# 14_RK3568_USBPCIeSATA_PHY.net
KiCad netlist of a schematic drawn in Altium Designer
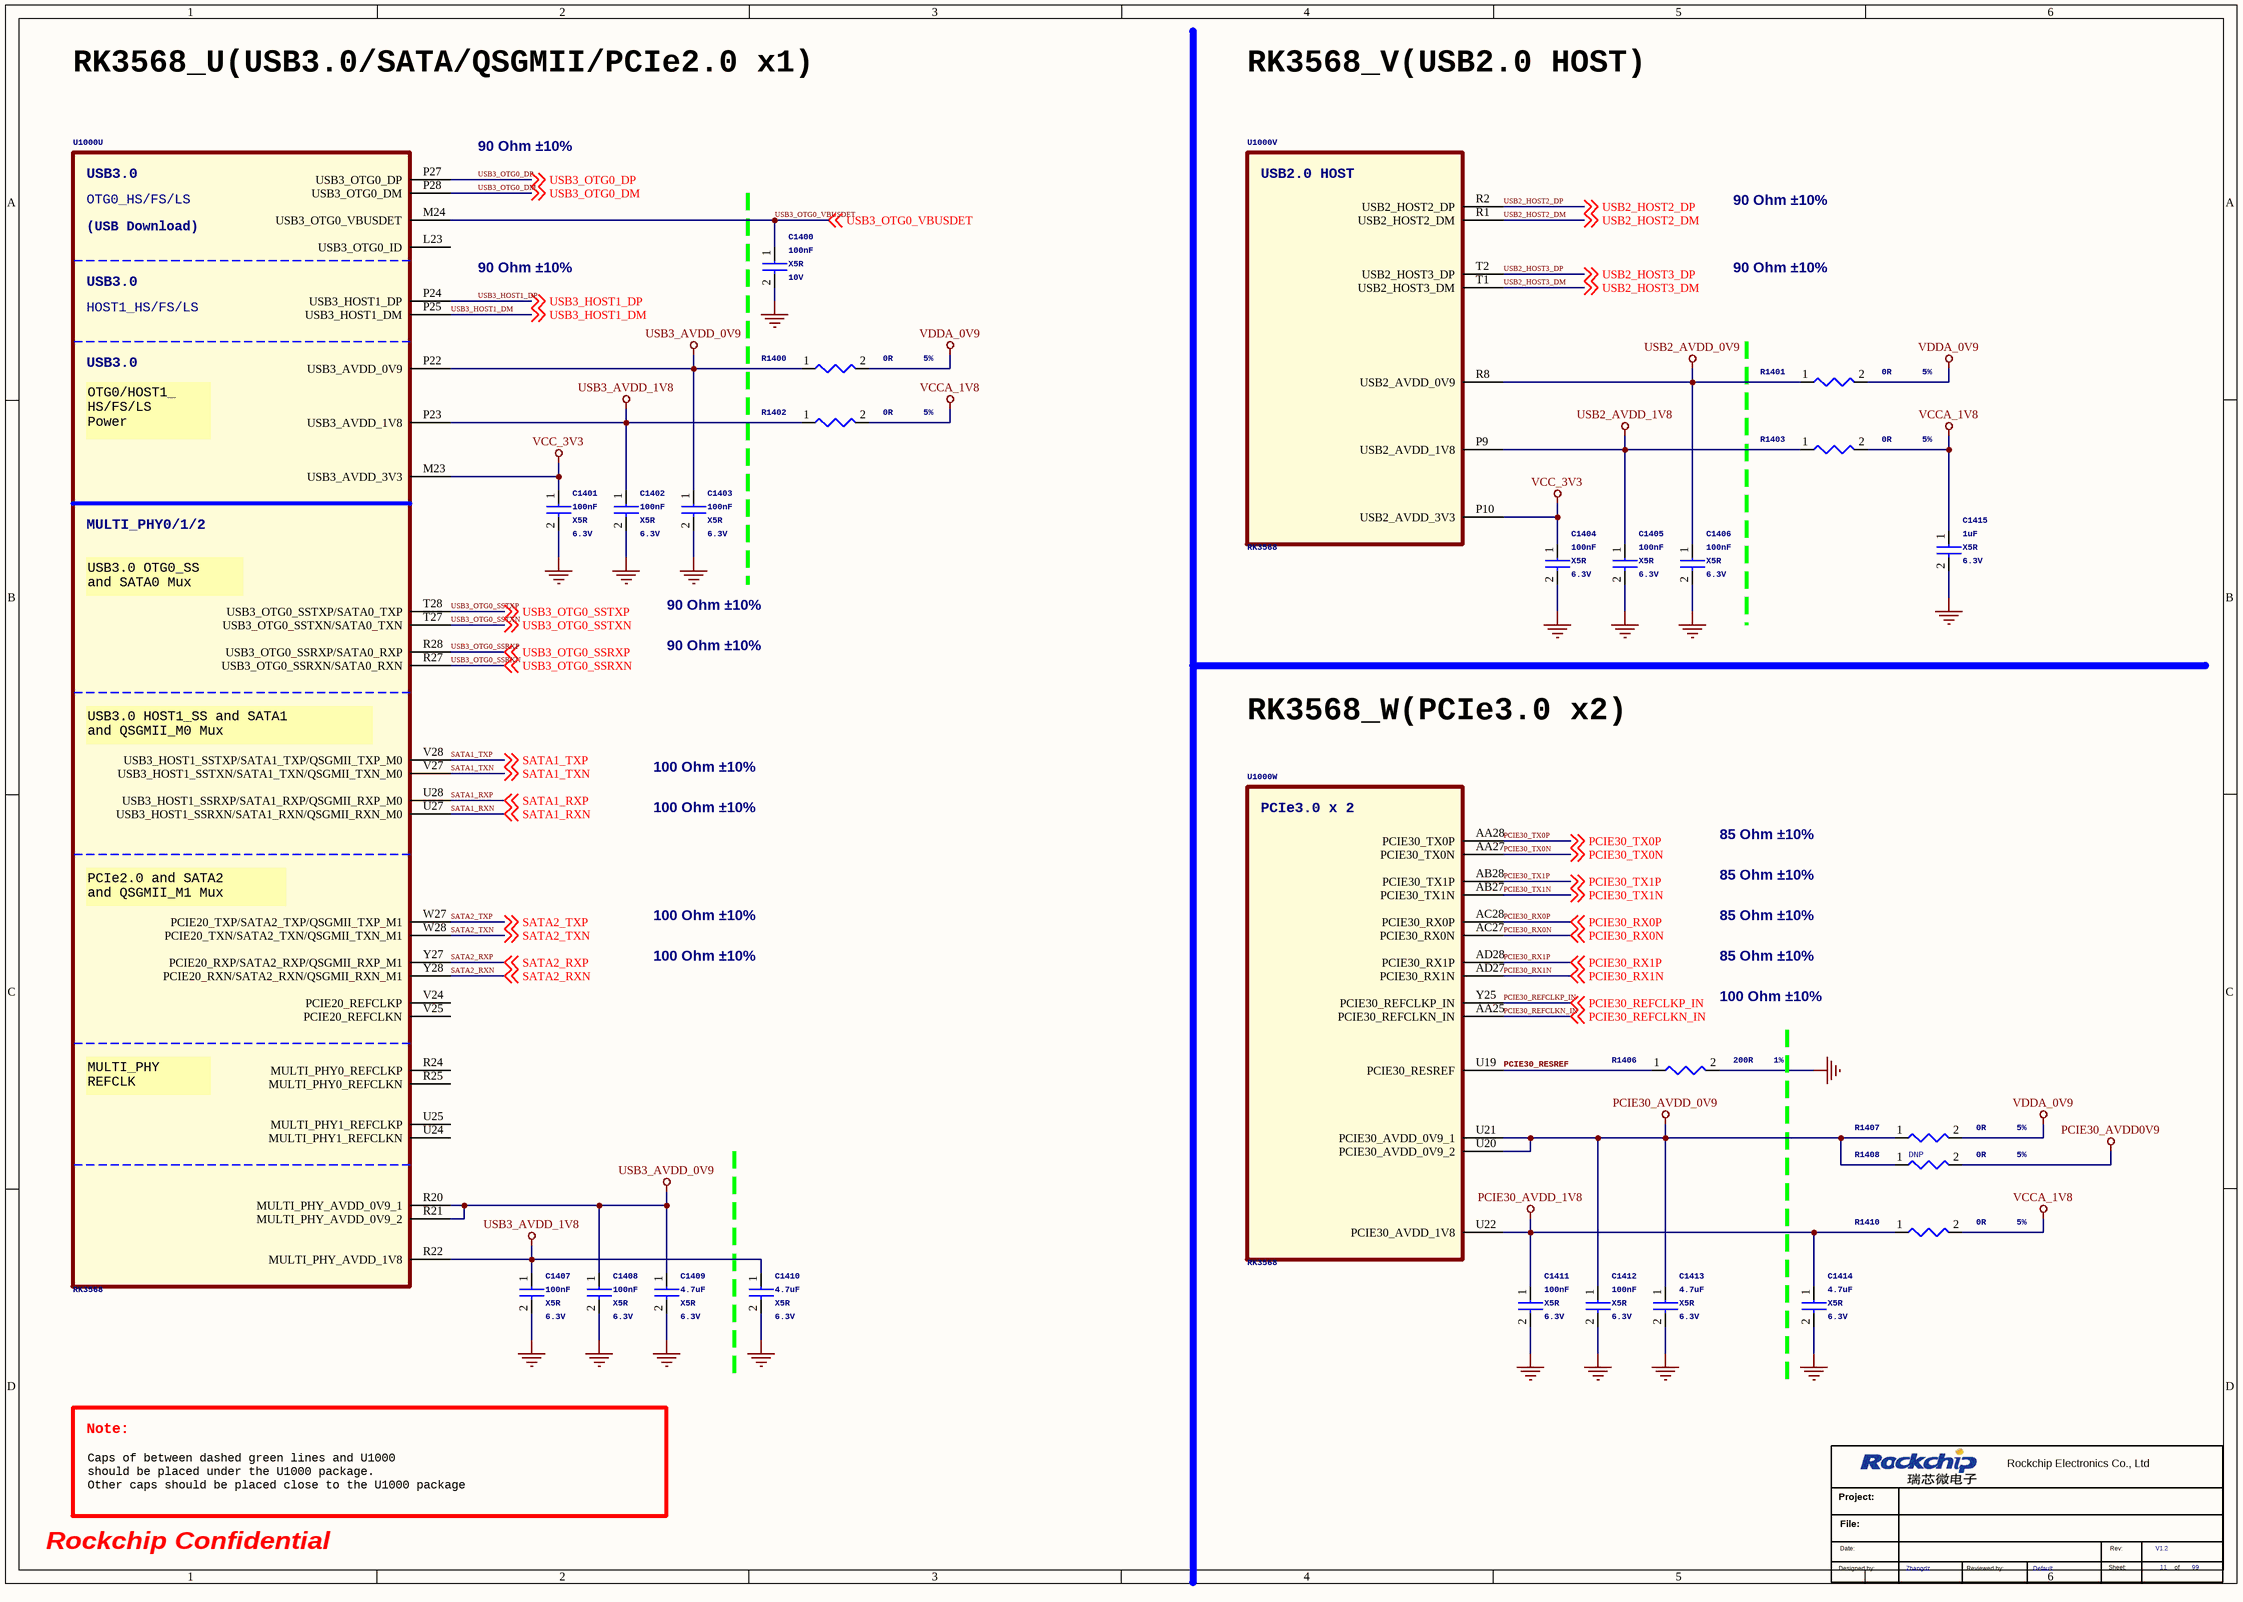
[diagram p0: 14.RK3568_USBPCIeSATA PHY.SchDoc]

(export (version "E")
  (design (tool "Eeschema 10.0.6"))
  (components
    (comp (ref "*")
      (value "Rockchip_new")
      (fields
        (field (name "SCHEMATIC PAGE COUNT") "99")
        (field (name "SCHEMATIC PAGE NUMBER") "11")
        (field (name "DESIGNER") "Zhangdz")
        (field (name "REVISION") "V1.2")
        (field (name "CHECK") "Default")
      )
      (libsource (lib "*") (part "Rockchip_new"))
    )
    (comp (ref "C1400")
      (value "100nF")
      (footprint "C0402")
      (description "cap,100.00nF,+/-10%,10V,X5R,C0402")
      (fields
        (field (name "VOLTAGE") "10V")
        (field (name "DIELECTRIC") "X5R")
        (field (name "MANUFACTURER") "TDK")
        (field (name "TOLERANCE") "10%")
        (field (name "CREATED BY") "JJJ")
      )
      (libsource (lib "*") (part "CAP NP"))
    )
    (comp (ref "C1401")
      (value "100nF")
      (footprint "C0201")
      (description "cap,100.00nF,+/-10%,6.3V,X5R,C0201")
      (fields
        (field (name "VOLTAGE") "6.3V")
        (field (name "DIELECTRIC") "X5R")
        (field (name "MANUFACTURER") "TDK")
        (field (name "TOLERANCE") "10%")
        (field (name "CREATED BY") "JJJ")
      )
      (libsource (lib "*") (part "CAP NP"))
    )
    (comp (ref "C1402")
      (value "100nF")
      (footprint "C0201")
      (description "cap,100.00nF,+/-10%,6.3V,X5R,C0201")
      (fields
        (field (name "VOLTAGE") "6.3V")
        (field (name "DIELECTRIC") "X5R")
        (field (name "MANUFACTURER") "TDK")
        (field (name "TOLERANCE") "10%")
        (field (name "CREATED BY") "JJJ")
      )
      (libsource (lib "*") (part "CAP NP"))
    )
    (comp (ref "C1403")
      (value "100nF")
      (footprint "C0201")
      (description "cap,100.00nF,+/-10%,6.3V,X5R,C0201")
      (fields
        (field (name "VOLTAGE") "6.3V")
        (field (name "DIELECTRIC") "X5R")
        (field (name "MANUFACTURER") "TDK")
        (field (name "TOLERANCE") "10%")
        (field (name "CREATED BY") "JJJ")
      )
      (libsource (lib "*") (part "CAP NP"))
    )
    (comp (ref "C1404")
      (value "100nF")
      (footprint "C0201")
      (description "cap,100.00nF,+/-10%,6.3V,X5R,C0201")
      (fields
        (field (name "VOLTAGE") "6.3V")
        (field (name "DIELECTRIC") "X5R")
        (field (name "MANUFACTURER") "TDK")
        (field (name "TOLERANCE") "10%")
        (field (name "CREATED BY") "JJJ")
      )
      (libsource (lib "*") (part "CAP NP"))
    )
    (comp (ref "C1405")
      (value "100nF")
      (footprint "C0201")
      (description "cap,100.00nF,+/-10%,6.3V,X5R,C0201")
      (fields
        (field (name "VOLTAGE") "6.3V")
        (field (name "DIELECTRIC") "X5R")
        (field (name "MANUFACTURER") "TDK")
        (field (name "TOLERANCE") "10%")
        (field (name "CREATED BY") "JJJ")
      )
      (libsource (lib "*") (part "CAP NP"))
    )
    (comp (ref "C1406")
      (value "100nF")
      (footprint "C0201")
      (description "cap,100.00nF,+/-10%,6.3V,X5R,C0201")
      (fields
        (field (name "VOLTAGE") "6.3V")
        (field (name "DIELECTRIC") "X5R")
        (field (name "MANUFACTURER") "TDK")
        (field (name "TOLERANCE") "10%")
        (field (name "CREATED BY") "JJJ")
      )
      (libsource (lib "*") (part "CAP NP"))
    )
    (comp (ref "C1407")
      (value "100nF")
      (footprint "C0201")
      (description "cap,100.00nF,+/-10%,6.3V,X5R,C0201")
      (fields
        (field (name "VOLTAGE") "6.3V")
        (field (name "DIELECTRIC") "X5R")
        (field (name "MANUFACTURER") "TDK")
        (field (name "TOLERANCE") "10%")
        (field (name "CREATED BY") "JJJ")
      )
      (libsource (lib "*") (part "CAP NP"))
    )
    (comp (ref "C1408")
      (value "100nF")
      (footprint "C0201")
      (description "cap,100.00nF,+/-10%,6.3V,X5R,C0201")
      (fields
        (field (name "VOLTAGE") "6.3V")
        (field (name "DIELECTRIC") "X5R")
        (field (name "MANUFACTURER") "TDK")
        (field (name "TOLERANCE") "10%")
        (field (name "CREATED BY") "JJJ")
      )
      (libsource (lib "*") (part "CAP NP"))
    )
    (comp (ref "C1409")
      (value "4.7uF")
      (footprint "C0402")
      (description "cap,4.70uF,+/-10%,6.3V,X5R,C0402")
      (fields
        (field (name "VOLTAGE") "6.3V")
        (field (name "DIELECTRIC") "X5R")
        (field (name "MANUFACTURER") "TDK")
        (field (name "TOLERANCE") "10%")
        (field (name "CREATED BY") "JJJ")
      )
      (libsource (lib "*") (part "CAP NP"))
    )
    (comp (ref "C1410")
      (value "4.7uF")
      (footprint "C0402")
      (description "cap,4.70uF,+/-10%,6.3V,X5R,C0402")
      (fields
        (field (name "VOLTAGE") "6.3V")
        (field (name "DIELECTRIC") "X5R")
        (field (name "MANUFACTURER") "TDK")
        (field (name "TOLERANCE") "10%")
        (field (name "CREATED BY") "JJJ")
      )
      (libsource (lib "*") (part "CAP NP"))
    )
    (comp (ref "C1411")
      (value "100nF")
      (footprint "C0201")
      (description "cap,100.00nF,+/-10%,6.3V,X5R,C0201")
      (fields
        (field (name "VOLTAGE") "6.3V")
        (field (name "DIELECTRIC") "X5R")
        (field (name "TOLERANCE") "10%")
        (field (name "MANUFACTURER") "TDK")
        (field (name "CREATED BY") "JJJ")
      )
      (libsource (lib "*") (part "CAP NP"))
    )
    (comp (ref "C1412")
      (value "100nF")
      (footprint "C0201")
      (description "cap,100.00nF,+/-10%,6.3V,X5R,C0201")
      (fields
        (field (name "VOLTAGE") "6.3V")
        (field (name "DIELECTRIC") "X5R")
        (field (name "MANUFACTURER") "TDK")
        (field (name "TOLERANCE") "10%")
        (field (name "CREATED BY") "JJJ")
      )
      (libsource (lib "*") (part "CAP NP"))
    )
    (comp (ref "C1413")
      (value "4.7uF")
      (footprint "C0402")
      (description "cap,4.70uF,+/-10%,6.3V,X5R,C0402")
      (fields
        (field (name "VOLTAGE") "6.3V")
        (field (name "DIELECTRIC") "X5R")
        (field (name "MANUFACTURER") "TDK")
        (field (name "TOLERANCE") "10%")
        (field (name "CREATED BY") "JJJ")
      )
      (libsource (lib "*") (part "CAP NP"))
    )
    (comp (ref "C1414")
      (value "4.7uF")
      (footprint "C0402")
      (description "cap,4.70uF,+/-10%,6.3V,X5R,C0402")
      (fields
        (field (name "VOLTAGE") "6.3V")
        (field (name "DIELECTRIC") "X5R")
        (field (name "MANUFACTURER") "TDK")
        (field (name "TOLERANCE") "10%")
        (field (name "CREATED BY") "JJJ")
      )
      (libsource (lib "*") (part "CAP NP"))
    )
    (comp (ref "C1415")
      (value "1uF")
      (footprint "C0402")
      (description "cap,1.00uF,+/-10%,6.3V,X5R,C0402")
      (fields
        (field (name "VOLTAGE") "6.3V")
        (field (name "DIELECTRIC") "X5R")
        (field (name "TOLERANCE") "10%")
        (field (name "MANUFACTURER") "TDK")
        (field (name "CREATED BY") "JJJ")
      )
      (libsource (lib "*") (part "CAP NP"))
    )
    (comp (ref "R1400")
      (value "0R")
      (footprint "R0402")
      (description "通用厚膜电阻,0R,+/-5%,R0402,1/16W.")
      (fields
        (field (name "TOLERANCE") "5%")
        (field (name "MANUFACTURER") "YAGEO")
        (field (name "CREATED BY") "YTL")
      )
      (libsource (lib "*") (part "RESISTOR"))
    )
    (comp (ref "R1401")
      (value "0R")
      (footprint "R0402")
      (description "通用厚膜电阻,0R,+/-5%,R0402,1/16W.")
      (fields
        (field (name "TOLERANCE") "5%")
        (field (name "MANUFACTURER") "YAGEO")
        (field (name "CREATED BY") "YTL")
      )
      (libsource (lib "*") (part "RESISTOR"))
    )
    (comp (ref "R1402")
      (value "0R")
      (footprint "R0402")
      (description "通用厚膜电阻,0R,+/-5%,R0402,1/16W.")
      (fields
        (field (name "TOLERANCE") "5%")
        (field (name "MANUFACTURER") "YAGEO")
        (field (name "CREATED BY") "YTL")
      )
      (libsource (lib "*") (part "RESISTOR"))
    )
    (comp (ref "R1403")
      (value "0R")
      (footprint "R0402")
      (description "通用厚膜电阻,0R,+/-5%,R0402,1/16W.")
      (fields
        (field (name "TOLERANCE") "5%")
        (field (name "MANUFACTURER") "YAGEO")
        (field (name "CREATED BY") "YTL")
      )
      (libsource (lib "*") (part "RESISTOR"))
    )
    (comp (ref "R1406")
      (value "200R")
      (footprint "R0201")
      (description "通用厚膜电阻,200R,+/-1%,R0201,1/20W.")
      (fields
        (field (name "TOLERANCE") "1%")
        (field (name "MANUFACTURER") "YAGEO")
        (field (name "CREATED BY") "YTL")
      )
      (libsource (lib "*") (part "RESISTOR"))
    )
    (comp (ref "R1407")
      (value "0R")
      (footprint "R0402")
      (description "通用厚膜电阻,0R,+/-5%,R0402,1/16W.")
      (fields
        (field (name "TOLERANCE") "5%")
        (field (name "MANUFACTURER") "YAGEO")
        (field (name "CREATED BY") "YTL")
      )
      (libsource (lib "*") (part "RESISTOR"))
    )
    (comp (ref "R1408")
      (value "0R")
      (footprint "R0402")
      (description "通用厚膜电阻,0R,+/-5%,R0402,1/16W.")
      (fields
        (field (name "TOLERANCE") "5%")
        (field (name "MANUFACTURER") "YAGEO")
        (field (name "OPTION") "DNP")
        (field (name "CREATED BY") "YTL")
      )
      (libsource (lib "*") (part "RESISTOR"))
    )
    (comp (ref "R1410")
      (value "0R")
      (footprint "R0402")
      (description "通用厚膜电阻,0R,+/-5%,R0402,1/16W.")
      (fields
        (field (name "TOLERANCE") "5%")
        (field (name "MANUFACTURER") "YAGEO")
        (field (name "CREATED BY") "YTL")
      )
      (libsource (lib "*") (part "RESISTOR"))
    )
    (comp (ref "U1000")
      (value "RK3568")
      (footprint "BGA636_19R00X19R00X1R20")
      (description "ROCKCHIP SOC")
      (fields (field (name "MANUFACTURER") "Rockchip (瑞芯微)") (field (name "CREATED BY") "JJJ"))
      (libsource (lib "*") (part "SOC_RK3568"))
    )
  )
  (nets
    (net (code "1") (name "/PCIE30_RESREF") (class "Default")
      (node (ref "R1406") (pin "1") (pinfunction "1_1") (pintype "passive"))
      (node (ref "U1000") (pin "U19") (pinfunction "PCIE30_RESREF_U19") (pintype "passive"))
    )
    (net (code "2") (name "GND") (class "Default")
      (node (ref "C1400") (pin "2") (pinfunction "2_2") (pintype "passive"))
      (node (ref "C1401") (pin "2") (pinfunction "2_2") (pintype "passive"))
      (node (ref "C1402") (pin "2") (pinfunction "2_2") (pintype "passive"))
      (node (ref "C1403") (pin "2") (pinfunction "2_2") (pintype "passive"))
      (node (ref "C1404") (pin "2") (pinfunction "2_2") (pintype "passive"))
      (node (ref "C1405") (pin "2") (pinfunction "2_2") (pintype "passive"))
      (node (ref "C1406") (pin "2") (pinfunction "2_2") (pintype "passive"))
      (node (ref "C1407") (pin "2") (pinfunction "2_2") (pintype "passive"))
      (node (ref "C1408") (pin "2") (pinfunction "2_2") (pintype "passive"))
      (node (ref "C1409") (pin "2") (pinfunction "2_2") (pintype "passive"))
      (node (ref "C1410") (pin "2") (pinfunction "2_2") (pintype "passive"))
      (node (ref "C1411") (pin "2") (pinfunction "2_2") (pintype "passive"))
      (node (ref "C1412") (pin "2") (pinfunction "2_2") (pintype "passive"))
      (node (ref "C1413") (pin "2") (pinfunction "2_2") (pintype "passive"))
      (node (ref "C1414") (pin "2") (pinfunction "2_2") (pintype "passive"))
      (node (ref "C1415") (pin "2") (pinfunction "2_2") (pintype "passive"))
      (node (ref "R1406") (pin "2") (pinfunction "2_2") (pintype "passive"))
    )
    (net (code "3") (name "PCIE30_AVDD0V9") (class "Default")
      (node (ref "R1408") (pin "2") (pinfunction "2_2") (pintype "passive"))
    )
    (net (code "4") (name "PCIE30_AVDD_0V9") (class "Default")
      (node (ref "C1412") (pin "1") (pinfunction "1_1") (pintype "passive"))
      (node (ref "C1413") (pin "1") (pinfunction "1_1") (pintype "passive"))
      (node (ref "R1407") (pin "1") (pinfunction "1_1") (pintype "passive"))
      (node (ref "R1408") (pin "1") (pinfunction "1_1") (pintype "passive"))
      (node (ref "U1000") (pin "U20") (pinfunction "PCIE30_AVDD_0V9_2_U20") (pintype "passive"))
      (node (ref "U1000") (pin "U21") (pinfunction "PCIE30_AVDD_0V9_1_U21") (pintype "passive"))
    )
    (net (code "5") (name "PCIE30_AVDD_1V8") (class "Default")
      (node (ref "C1411") (pin "1") (pinfunction "1_1") (pintype "passive"))
      (node (ref "C1414") (pin "1") (pinfunction "1_1") (pintype "passive"))
      (node (ref "R1410") (pin "1") (pinfunction "1_1") (pintype "passive"))
      (node (ref "U1000") (pin "U22") (pinfunction "PCIE30_AVDD_1V8_U22") (pintype "passive"))
    )
    (net (code "6") (name "PCIE30_REFCLKN_IN") (class "Default")
      (node (ref "U1000") (pin "AA25") (pinfunction "PCIE30_REFCLKN_IN_AA25") (pintype "passive"))
    )
    (net (code "7") (name "PCIE30_REFCLKP_IN") (class "Default")
      (node (ref "U1000") (pin "Y25") (pinfunction "PCIE30_REFCLKP_IN_Y25") (pintype "passive"))
    )
    (net (code "8") (name "PCIE30_RX0N") (class "Default")
      (node (ref "U1000") (pin "AC27") (pinfunction "PCIE30_RX0N_AC27") (pintype "passive"))
    )
    (net (code "9") (name "PCIE30_RX0P") (class "Default")
      (node (ref "U1000") (pin "AC28") (pinfunction "PCIE30_RX0P_AC28") (pintype "passive"))
    )
    (net (code "10") (name "PCIE30_RX1N") (class "Default")
      (node (ref "U1000") (pin "AD27") (pinfunction "PCIE30_RX1N_AD27") (pintype "passive"))
    )
    (net (code "11") (name "PCIE30_RX1P") (class "Default")
      (node (ref "U1000") (pin "AD28") (pinfunction "PCIE30_RX1P_AD28") (pintype "passive"))
    )
    (net (code "12") (name "PCIE30_TX0N") (class "Default")
      (node (ref "U1000") (pin "AA27") (pinfunction "PCIE30_TX0N_AA27") (pintype "passive"))
    )
    (net (code "13") (name "PCIE30_TX0P") (class "Default")
      (node (ref "U1000") (pin "AA28") (pinfunction "PCIE30_TX0P_AA28") (pintype "passive"))
    )
    (net (code "14") (name "PCIE30_TX1N") (class "Default")
      (node (ref "U1000") (pin "AB27") (pinfunction "PCIE30_TX1N_AB27") (pintype "passive"))
    )
    (net (code "15") (name "PCIE30_TX1P") (class "Default")
      (node (ref "U1000") (pin "AB28") (pinfunction "PCIE30_TX1P_AB28") (pintype "passive"))
    )
    (net (code "16") (name "SATA1_RXN") (class "Default")
      (node (ref "U1000") (pin "U27") (pinfunction "USB3_HOST1_SSRXN/SATA1_RXN/QSGMII_RXN_M0_U27") (pintype "passive"))
    )
    (net (code "17") (name "SATA1_RXP") (class "Default")
      (node (ref "U1000") (pin "U28") (pinfunction "USB3_HOST1_SSRXP/SATA1_RXP/QSGMII_RXP_M0_U28") (pintype "passive"))
    )
    (net (code "18") (name "SATA1_TXN") (class "Default")
      (node (ref "U1000") (pin "V27") (pinfunction "USB3_HOST1_SSTXN/SATA1_TXN/QSGMII_TXN_M0_V27") (pintype "passive"))
    )
    (net (code "19") (name "SATA1_TXP") (class "Default")
      (node (ref "U1000") (pin "V28") (pinfunction "USB3_HOST1_SSTXP/SATA1_TXP/QSGMII_TXP_M0_V28") (pintype "passive"))
    )
    (net (code "20") (name "SATA2_RXN") (class "Default")
      (node (ref "U1000") (pin "Y28") (pinfunction "PCIE20_RXN/SATA2_RXN/QSGMII_RXN_M1_Y28") (pintype "passive"))
    )
    (net (code "21") (name "SATA2_RXP") (class "Default")
      (node (ref "U1000") (pin "Y27") (pinfunction "PCIE20_RXP/SATA2_RXP/QSGMII_RXP_M1_Y27") (pintype "passive"))
    )
    (net (code "22") (name "SATA2_TXN") (class "Default")
      (node (ref "U1000") (pin "W28") (pinfunction "PCIE20_TXN/SATA2_TXN/QSGMII_TXN_M1_W28") (pintype "passive"))
    )
    (net (code "23") (name "SATA2_TXP") (class "Default")
      (node (ref "U1000") (pin "W27") (pinfunction "PCIE20_TXP/SATA2_TXP/QSGMII_TXP_M1_W27") (pintype "passive"))
    )
    (net (code "24") (name "USB2_AVDD_0V9") (class "Default")
      (node (ref "C1406") (pin "1") (pinfunction "1_1") (pintype "passive"))
      (node (ref "R1401") (pin "1") (pinfunction "1_1") (pintype "passive"))
      (node (ref "U1000") (pin "R8") (pinfunction "USB2_AVDD_0V9_R8") (pintype "passive"))
    )
    (net (code "25") (name "USB2_AVDD_1V8") (class "Default")
      (node (ref "C1405") (pin "1") (pinfunction "1_1") (pintype "passive"))
      (node (ref "R1403") (pin "1") (pinfunction "1_1") (pintype "passive"))
      (node (ref "U1000") (pin "P9") (pinfunction "USB2_AVDD_1V8_P9") (pintype "passive"))
    )
    (net (code "26") (name "USB2_HOST2_DM") (class "Default")
      (node (ref "U1000") (pin "R1") (pinfunction "USB2_HOST2_DM_R1") (pintype "passive"))
    )
    (net (code "27") (name "USB2_HOST2_DP") (class "Default")
      (node (ref "U1000") (pin "R2") (pinfunction "USB2_HOST2_DP_R2") (pintype "passive"))
    )
    (net (code "28") (name "USB2_HOST3_DM") (class "Default")
      (node (ref "U1000") (pin "T1") (pinfunction "USB2_HOST3_DM_T1") (pintype "passive"))
    )
    (net (code "29") (name "USB2_HOST3_DP") (class "Default")
      (node (ref "U1000") (pin "T2") (pinfunction "USB2_HOST3_DP_T2") (pintype "passive"))
    )
    (net (code "30") (name "USB3_AVDD_0V9") (class "Default")
      (node (ref "C1403") (pin "1") (pinfunction "1_1") (pintype "passive"))
      (node (ref "C1408") (pin "1") (pinfunction "1_1") (pintype "passive"))
      (node (ref "C1409") (pin "1") (pinfunction "1_1") (pintype "passive"))
      (node (ref "R1400") (pin "1") (pinfunction "1_1") (pintype "passive"))
      (node (ref "U1000") (pin "P22") (pinfunction "USB3_AVDD_0V9_P22") (pintype "passive"))
      (node (ref "U1000") (pin "R20") (pinfunction "MULTI_PHY_AVDD_0V9_1_R20") (pintype "passive"))
      (node (ref "U1000") (pin "R21") (pinfunction "MULTI_PHY_AVDD_0V9_2_R21") (pintype "passive"))
    )
    (net (code "31") (name "USB3_AVDD_1V8") (class "Default")
      (node (ref "C1402") (pin "1") (pinfunction "1_1") (pintype "passive"))
      (node (ref "C1407") (pin "1") (pinfunction "1_1") (pintype "passive"))
      (node (ref "C1410") (pin "1") (pinfunction "1_1") (pintype "passive"))
      (node (ref "R1402") (pin "1") (pinfunction "1_1") (pintype "passive"))
      (node (ref "U1000") (pin "P23") (pinfunction "USB3_AVDD_1V8_P23") (pintype "passive"))
      (node (ref "U1000") (pin "R22") (pinfunction "MULTI_PHY_AVDD_1V8_R22") (pintype "passive"))
    )
    (net (code "32") (name "USB3_HOST1_DM") (class "Default")
      (node (ref "U1000") (pin "P25") (pinfunction "USB3_HOST1_DM_P25") (pintype "passive"))
    )
    (net (code "33") (name "USB3_HOST1_DP") (class "Default")
      (node (ref "U1000") (pin "P24") (pinfunction "USB3_HOST1_DP_P24") (pintype "passive"))
    )
    (net (code "34") (name "USB3_OTG0_DM") (class "Default")
      (node (ref "U1000") (pin "P28") (pinfunction "USB3_OTG0_DM_P28") (pintype "passive"))
    )
    (net (code "35") (name "USB3_OTG0_DP") (class "Default")
      (node (ref "U1000") (pin "P27") (pinfunction "USB3_OTG0_DP_P27") (pintype "passive"))
    )
    (net (code "36") (name "USB3_OTG0_SSRXN") (class "Default")
      (node (ref "U1000") (pin "R27") (pinfunction "USB3_OTG0_SSRXN/SATA0_RXN_R27") (pintype "passive"))
    )
    (net (code "37") (name "USB3_OTG0_SSRXP") (class "Default")
      (node (ref "U1000") (pin "R28") (pinfunction "USB3_OTG0_SSRXP/SATA0_RXP_R28") (pintype "passive"))
    )
    (net (code "38") (name "USB3_OTG0_SSTXN") (class "Default")
      (node (ref "U1000") (pin "T27") (pinfunction "USB3_OTG0_SSTXN/SATA0_TXN_T27") (pintype "passive"))
    )
    (net (code "39") (name "USB3_OTG0_SSTXP") (class "Default")
      (node (ref "U1000") (pin "T28") (pinfunction "USB3_OTG0_SSTXP/SATA0_TXP_T28") (pintype "passive"))
    )
    (net (code "40") (name "USB3_OTG0_VBUSDET") (class "Default")
      (node (ref "C1400") (pin "1") (pinfunction "1_1") (pintype "passive"))
      (node (ref "U1000") (pin "M24") (pinfunction "USB3_OTG0_VBUSDET_M24") (pintype "passive"))
    )
    (net (code "41") (name "VCCA_1V8") (class "Default")
      (node (ref "C1415") (pin "1") (pinfunction "1_1") (pintype "passive"))
      (node (ref "R1402") (pin "2") (pinfunction "2_2") (pintype "passive"))
      (node (ref "R1403") (pin "2") (pinfunction "2_2") (pintype "passive"))
      (node (ref "R1410") (pin "2") (pinfunction "2_2") (pintype "passive"))
    )
    (net (code "42") (name "VCC_3V3") (class "Default")
      (node (ref "C1401") (pin "1") (pinfunction "1_1") (pintype "passive"))
      (node (ref "C1404") (pin "1") (pinfunction "1_1") (pintype "passive"))
      (node (ref "U1000") (pin "M23") (pinfunction "USB3_AVDD_3V3_M23") (pintype "passive"))
      (node (ref "U1000") (pin "P10") (pinfunction "USB2_AVDD_3V3_P10") (pintype "passive"))
    )
    (net (code "43") (name "VDDA_0V9") (class "Default")
      (node (ref "R1400") (pin "2") (pinfunction "2_2") (pintype "passive"))
      (node (ref "R1401") (pin "2") (pinfunction "2_2") (pintype "passive"))
      (node (ref "R1407") (pin "2") (pinfunction "2_2") (pintype "passive"))
    )
    (net (code "44") (name "unconnected-(U1000U-MULTI_PHY0_REFCLKN-PadR25)") (class "Default")
      (node (ref "U1000") (pin "R25") (pinfunction "MULTI_PHY0_REFCLKN_R25") (pintype "passive"))
    )
    (net (code "45") (name "unconnected-(U1000U-MULTI_PHY0_REFCLKP-PadR24)") (class "Default")
      (node (ref "U1000") (pin "R24") (pinfunction "MULTI_PHY0_REFCLKP_R24") (pintype "passive"))
    )
    (net (code "46") (name "unconnected-(U1000U-MULTI_PHY1_REFCLKN-PadU24)") (class "Default")
      (node (ref "U1000") (pin "U24") (pinfunction "MULTI_PHY1_REFCLKN_U24") (pintype "passive"))
    )
    (net (code "47") (name "unconnected-(U1000U-MULTI_PHY1_REFCLKP-PadU25)") (class "Default")
      (node (ref "U1000") (pin "U25") (pinfunction "MULTI_PHY1_REFCLKP_U25") (pintype "passive"))
    )
    (net (code "48") (name "unconnected-(U1000U-PCIE20_REFCLKN-PadV25)") (class "Default")
      (node (ref "U1000") (pin "V25") (pinfunction "PCIE20_REFCLKN_V25") (pintype "passive"))
    )
    (net (code "49") (name "unconnected-(U1000U-PCIE20_REFCLKP-PadV24)") (class "Default")
      (node (ref "U1000") (pin "V24") (pinfunction "PCIE20_REFCLKP_V24") (pintype "passive"))
    )
    (net (code "50") (name "unconnected-(U1000U-USB3_OTG0_ID-PadL23)") (class "Default")
      (node (ref "U1000") (pin "L23") (pinfunction "USB3_OTG0_ID_L23") (pintype "passive"))
    )
  )
)
